# Zio_Qwiic_1_5in_OLED_Display.net
KiCad netlist of a schematic drawn in EAGLE
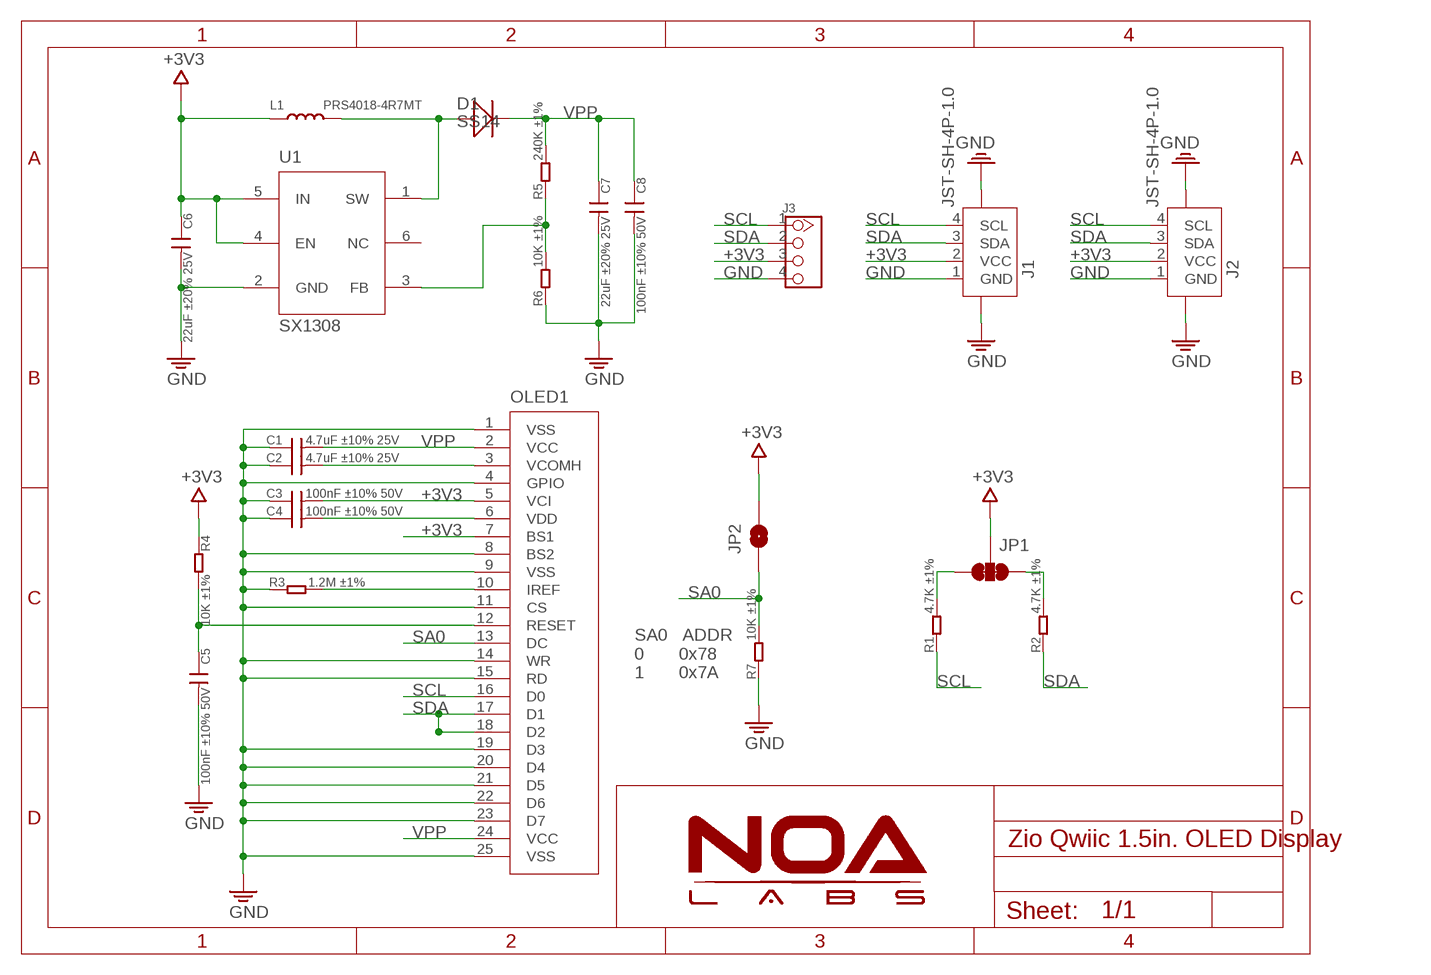
[diagram p0: schematic, sheet 1]

(export (version "E")
  (design (tool "Eeschema 10.0.6"))
  (components
    (comp (ref "C1")
      (value "4.7uF ±10% 25V")
      (footprint "eagle-import:C0603")
      (libsource (lib "eagle-import") (part "C-0603"))
    )
    (comp (ref "C2")
      (value "4.7uF ±10% 25V")
      (footprint "eagle-import:C0603")
      (libsource (lib "eagle-import") (part "C-0603"))
    )
    (comp (ref "C3")
      (value "100nF ±10% 50V")
      (footprint "eagle-import:C0603")
      (libsource (lib "eagle-import") (part "C-0603"))
    )
    (comp (ref "C4")
      (value "100nF ±10% 50V")
      (footprint "eagle-import:C0603")
      (libsource (lib "eagle-import") (part "C-0603"))
    )
    (comp (ref "C5")
      (value "100nF ±10% 50V")
      (footprint "eagle-import:C0603")
      (libsource (lib "eagle-import") (part "C-0603"))
    )
    (comp (ref "C6")
      (value "22uF ±20% 25V")
      (footprint "eagle-import:C0805")
      (libsource (lib "eagle-import") (part "C-0805"))
    )
    (comp (ref "C7")
      (value "22uF ±20% 25V")
      (footprint "eagle-import:C0805")
      (libsource (lib "eagle-import") (part "C-0805"))
    )
    (comp (ref "C8")
      (value "100nF ±10% 50V")
      (footprint "eagle-import:C0603")
      (libsource (lib "eagle-import") (part "C-0603"))
    )
    (comp (ref "D1")
      (value "SS14")
      (footprint "eagle-import:DO-214AC")
      (libsource (lib "eagle-import") (part "D214AA"))
    )
    (comp (ref "J1")
      (value "JST-SH-4P-1.0")
      (footprint "eagle-import:JST-SH-4P")
      (libsource (lib "eagle-import") (part "JST-SH-4P-1.0"))
    )
    (comp (ref "J2")
      (value "JST-SH-4P-1.0")
      (footprint "eagle-import:JST-SH-4P")
      (libsource (lib "eagle-import") (part "JST-SH-4P-1.0"))
    )
    (comp (ref "J3")
      (value "HEADER-4P-60/35MIL")
      (footprint "eagle-import:4P-65_35MIL")
      (libsource (lib "eagle-import") (part "HEADER-4P-60/35MIL"))
    )
    (comp (ref "JP1")
      (value "SMT-JUMPER_3_2-NC_TRACE")
      (footprint "eagle-import:SMT-JUMPER_3_2-NC_TRACE")
      (libsource (lib "eagle-import") (part "SMT-JUMPER_3_2-NC_TRACE"))
    )
    (comp (ref "JP2")
      (value "JUMPER-SMT_2_NC_PASTE_NOCREM")
      (footprint "eagle-import:SMT-JUMPER_2_NC_PASTE_SILK_NOCREM")
      (libsource (lib "eagle-import") (part "JUMPER-SMT_2_NC_PASTE_NOCREM"))
    )
    (comp (ref "L1")
      (value "PRS4018-4R7MT")
      (footprint "eagle-import:L4030")
      (libsource (lib "eagle-import") (part "L-4030"))
    )
    (comp (ref "OLED1")
      (value "OLED_MODULE_1.5IN_128128")
      (footprint "eagle-import:OLED_MODULE_1.5IN_128_128")
      (libsource (lib "eagle-import") (part "OLED_MODULE_1.5IN_128128"))
    )
    (comp (ref "R1")
      (value "4.7K ±1%")
      (footprint "eagle-import:R0603")
      (libsource (lib "eagle-import") (part "R-0603"))
    )
    (comp (ref "R2")
      (value "4.7K ±1%")
      (footprint "eagle-import:R0603")
      (libsource (lib "eagle-import") (part "R-0603"))
    )
    (comp (ref "R3")
      (value "1.2M ±1%")
      (footprint "eagle-import:R0603")
      (libsource (lib "eagle-import") (part "R-0603"))
    )
    (comp (ref "R4")
      (value "10K ±1%")
      (footprint "eagle-import:R0603")
      (libsource (lib "eagle-import") (part "R-0603"))
    )
    (comp (ref "R5")
      (value "240K ±1%")
      (footprint "eagle-import:R0603")
      (libsource (lib "eagle-import") (part "R-0603"))
    )
    (comp (ref "R6")
      (value "10K ±1%")
      (footprint "eagle-import:R0603")
      (libsource (lib "eagle-import") (part "R-0603"))
    )
    (comp (ref "R7")
      (value "10K ±1%")
      (footprint "eagle-import:R0603")
      (libsource (lib "eagle-import") (part "R-0603"))
    )
    (comp (ref "U1")
      (value "SX1308")
      (footprint "eagle-import:SOT23-6")
      (libsource (lib "eagle-import") (part "SX1308"))
    )
  )
  (nets
    (net (code "1") (name "+3V3") (class "Default")
      (node (ref "C3") (pin "2") (pinfunction "2_2") (pintype "passive"))
      (node (ref "C6") (pin "1") (pinfunction "1_1") (pintype "passive"))
      (node (ref "J1") (pin "2") (pinfunction "VCC_2") (pintype "bidirectional"))
      (node (ref "J2") (pin "2") (pinfunction "VCC_2") (pintype "bidirectional"))
      (node (ref "J3") (pin "3") (pinfunction "P$3_3") (pintype "bidirectional"))
      (node (ref "JP1") (pin "2") (pinfunction "2_2") (pintype "passive"))
      (node (ref "JP2") (pin "2") (pinfunction "2_2") (pintype "passive"))
      (node (ref "L1") (pin "1") (pinfunction "1_1") (pintype "passive"))
      (node (ref "OLED1") (pin "5") (pinfunction "VCI_5") (pintype "bidirectional"))
      (node (ref "OLED1") (pin "7") (pinfunction "BS1_7") (pintype "bidirectional"))
      (node (ref "R4") (pin "1") (pinfunction "1_1") (pintype "passive"))
      (node (ref "U1") (pin "4") (pinfunction "EN_4") (pintype "bidirectional"))
      (node (ref "U1") (pin "5") (pinfunction "IN_5") (pintype "bidirectional"))
    )
    (net (code "2") (name "/SA0") (class "Default")
      (node (ref "JP2") (pin "1") (pinfunction "1_1") (pintype "passive"))
      (node (ref "OLED1") (pin "13") (pinfunction "DC_13") (pintype "bidirectional"))
      (node (ref "R7") (pin "2") (pinfunction "2_2") (pintype "passive"))
    )
    (net (code "3") (name "/SCL") (class "Default")
      (node (ref "J1") (pin "4") (pinfunction "SCL_4") (pintype "bidirectional"))
      (node (ref "J2") (pin "4") (pinfunction "SCL_4") (pintype "bidirectional"))
      (node (ref "J3") (pin "1") (pinfunction "P$1_1") (pintype "bidirectional"))
      (node (ref "OLED1") (pin "16") (pinfunction "D0_16") (pintype "bidirectional"))
      (node (ref "R1") (pin "1") (pinfunction "1_1") (pintype "passive"))
    )
    (net (code "4") (name "/SDA") (class "Default")
      (node (ref "J1") (pin "3") (pinfunction "SDA_3") (pintype "bidirectional"))
      (node (ref "J2") (pin "3") (pinfunction "SDA_3") (pintype "bidirectional"))
      (node (ref "J3") (pin "2") (pinfunction "P$2_2") (pintype "bidirectional"))
      (node (ref "OLED1") (pin "17") (pinfunction "D1_17") (pintype "bidirectional"))
      (node (ref "OLED1") (pin "18") (pinfunction "D2_18") (pintype "bidirectional"))
      (node (ref "R2") (pin "1") (pinfunction "1_1") (pintype "passive"))
    )
    (net (code "5") (name "/VPP") (class "Default")
      (node (ref "C1") (pin "2") (pinfunction "2_2") (pintype "passive"))
      (node (ref "C7") (pin "1") (pinfunction "1_1") (pintype "passive"))
      (node (ref "C8") (pin "1") (pinfunction "1_1") (pintype "passive"))
      (node (ref "D1") (pin "C") (pinfunction "-_C") (pintype "passive"))
      (node (ref "OLED1") (pin "2") (pinfunction "VCC_2") (pintype "bidirectional"))
      (node (ref "OLED1") (pin "24") (pinfunction "VCC_24") (pintype "bidirectional"))
      (node (ref "R5") (pin "2") (pinfunction "2_2") (pintype "passive"))
    )
    (net (code "6") (name "GND") (class "Default")
      (node (ref "C1") (pin "1") (pinfunction "1_1") (pintype "passive"))
      (node (ref "C2") (pin "1") (pinfunction "1_1") (pintype "passive"))
      (node (ref "C3") (pin "1") (pinfunction "1_1") (pintype "passive"))
      (node (ref "C4") (pin "1") (pinfunction "1_1") (pintype "passive"))
      (node (ref "C5") (pin "2") (pinfunction "2_2") (pintype "passive"))
      (node (ref "C6") (pin "2") (pinfunction "2_2") (pintype "passive"))
      (node (ref "C7") (pin "2") (pinfunction "2_2") (pintype "passive"))
      (node (ref "C8") (pin "2") (pinfunction "2_2") (pintype "passive"))
      (node (ref "J1") (pin "1") (pinfunction "GND_1") (pintype "bidirectional"))
      (node (ref "J1") (pin "NC1") (pinfunction "5_NC1") (pintype "bidirectional"))
      (node (ref "J1") (pin "NC2") (pinfunction "6_NC2") (pintype "bidirectional"))
      (node (ref "J2") (pin "1") (pinfunction "GND_1") (pintype "bidirectional"))
      (node (ref "J2") (pin "NC1") (pinfunction "5_NC1") (pintype "bidirectional"))
      (node (ref "J2") (pin "NC2") (pinfunction "6_NC2") (pintype "bidirectional"))
      (node (ref "J3") (pin "4") (pinfunction "P$4_4") (pintype "bidirectional"))
      (node (ref "OLED1") (pin "1") (pinfunction "VSS_1") (pintype "bidirectional"))
      (node (ref "OLED1") (pin "11") (pinfunction "CS_11") (pintype "bidirectional"))
      (node (ref "OLED1") (pin "14") (pinfunction "WR_14") (pintype "bidirectional"))
      (node (ref "OLED1") (pin "15") (pinfunction "RD_15") (pintype "bidirectional"))
      (node (ref "OLED1") (pin "19") (pinfunction "D3_19") (pintype "bidirectional"))
      (node (ref "OLED1") (pin "20") (pinfunction "D4_20") (pintype "bidirectional"))
      (node (ref "OLED1") (pin "21") (pinfunction "D5_21") (pintype "bidirectional"))
      (node (ref "OLED1") (pin "22") (pinfunction "D6_22") (pintype "bidirectional"))
      (node (ref "OLED1") (pin "23") (pinfunction "D7_23") (pintype "bidirectional"))
      (node (ref "OLED1") (pin "25") (pinfunction "VSS_25") (pintype "bidirectional"))
      (node (ref "OLED1") (pin "4") (pinfunction "GPIO_4") (pintype "bidirectional"))
      (node (ref "OLED1") (pin "8") (pinfunction "BS2_8") (pintype "bidirectional"))
      (node (ref "OLED1") (pin "9") (pinfunction "VSS_9") (pintype "bidirectional"))
      (node (ref "R3") (pin "1") (pinfunction "1_1") (pintype "passive"))
      (node (ref "R6") (pin "1") (pinfunction "1_1") (pintype "passive"))
      (node (ref "R7") (pin "1") (pinfunction "1_1") (pintype "passive"))
      (node (ref "U1") (pin "2") (pinfunction "GND_2") (pintype "bidirectional"))
    )
    (net (code "7") (name "Net-(D1-+)") (class "Default")
      (node (ref "D1") (pin "A") (pinfunction "+_A") (pintype "passive"))
      (node (ref "L1") (pin "2") (pinfunction "2_2") (pintype "passive"))
      (node (ref "U1") (pin "1") (pinfunction "SW_1") (pintype "bidirectional"))
    )
    (net (code "8") (name "Net-(JP1-Pad1)") (class "Default")
      (node (ref "JP1") (pin "1") (pinfunction "1_1") (pintype "passive"))
      (node (ref "R2") (pin "2") (pinfunction "2_2") (pintype "passive"))
    )
    (net (code "9") (name "Net-(JP1-Pad3)") (class "Default")
      (node (ref "JP1") (pin "3") (pinfunction "3_3") (pintype "passive"))
      (node (ref "R1") (pin "2") (pinfunction "2_2") (pintype "passive"))
    )
    (net (code "10") (name "Net-(OLED1-IREF)") (class "Default")
      (node (ref "OLED1") (pin "10") (pinfunction "IREF_10") (pintype "bidirectional"))
      (node (ref "R3") (pin "2") (pinfunction "2_2") (pintype "passive"))
    )
    (net (code "11") (name "Net-(OLED1-RESET)") (class "Default")
      (node (ref "C5") (pin "1") (pinfunction "1_1") (pintype "passive"))
      (node (ref "OLED1") (pin "12") (pinfunction "RESET_12") (pintype "bidirectional"))
      (node (ref "R4") (pin "2") (pinfunction "2_2") (pintype "passive"))
    )
    (net (code "12") (name "Net-(OLED1-VCOMH)") (class "Default")
      (node (ref "C2") (pin "2") (pinfunction "2_2") (pintype "passive"))
      (node (ref "OLED1") (pin "3") (pinfunction "VCOMH_3") (pintype "bidirectional"))
    )
    (net (code "13") (name "Net-(OLED1-VDD)") (class "Default")
      (node (ref "C4") (pin "2") (pinfunction "2_2") (pintype "passive"))
      (node (ref "OLED1") (pin "6") (pinfunction "VDD_6") (pintype "bidirectional"))
    )
    (net (code "14") (name "Net-(U1-FB)") (class "Default")
      (node (ref "R5") (pin "1") (pinfunction "1_1") (pintype "passive"))
      (node (ref "R6") (pin "2") (pinfunction "2_2") (pintype "passive"))
      (node (ref "U1") (pin "3") (pinfunction "FB_3") (pintype "bidirectional"))
    )
    (net (code "15") (name "unconnected-(U1-NC-Pad6)") (class "Default")
      (node (ref "U1") (pin "6") (pinfunction "NC_6") (pintype "bidirectional"))
    )
  )
)
